# servo.net
KiCad netlist of a schematic drawn in Altium Designer
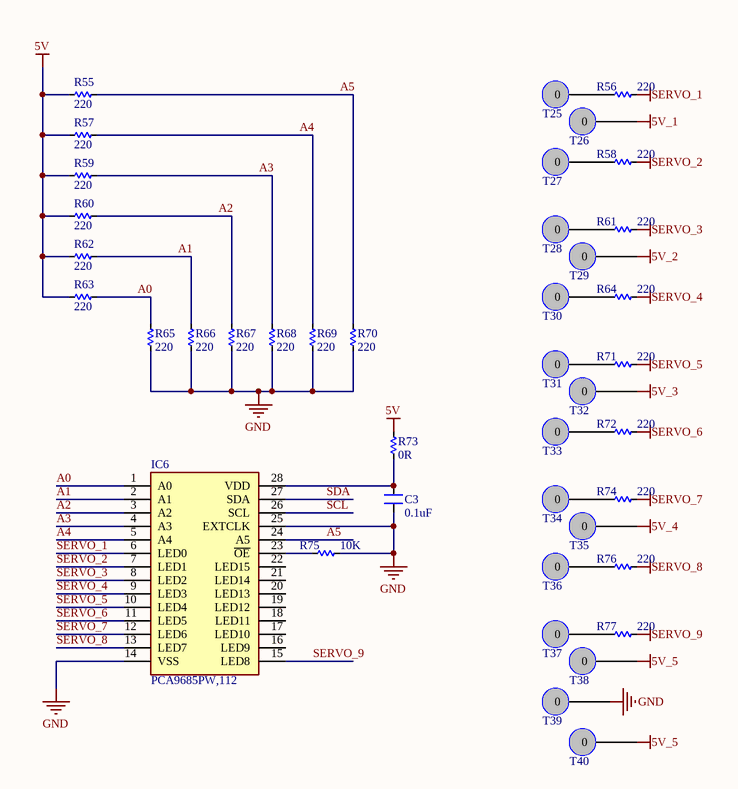
[diagram p0: servo.SchDoc]

(export (version "E")
  (design (tool "Eeschema 10.0.6"))
  (components
    (comp (ref "C3")
      (value "0.1uF")
      (footprint "CN-SMD-0603")
      (description "Tu gom")
      (libsource (lib "LIBTanCN") (part "CN"))
    )
    (comp (ref "IC6")
      (value "PCA9685PW,112")
      (footprint "SamacSys:SOP65P640X110-28N")
      (description "Integrated Circuit")
      (fields (field (name "MOUSER PART NUMBER") "771-PCA9685PW,112"))
      (libsource (lib "*") (part "PCA9685PW,112"))
    )
    (comp (ref "R55")
      (value "220")
      (footprint "RES-SMD-0603")
      (description "Resistor")
      (fields
        (field (name "MANUFACTURER") "Generic Components")
        (field (name "PUBLISHER") "Altium Hobart Technology Centre")
      )
      (libsource (lib "LIBRARY") (part "Res-SMD"))
    )
    (comp (ref "R56")
      (value "220")
      (footprint "RES-SMD-0603")
      (description "Resistor")
      (fields
        (field (name "MANUFACTURER") "Generic Components")
        (field (name "PUBLISHER") "Altium Hobart Technology Centre")
      )
      (libsource (lib "LIBRARY") (part "Res-SMD"))
    )
    (comp (ref "R57")
      (value "220")
      (footprint "RES-SMD-0603")
      (description "Resistor")
      (fields
        (field (name "MANUFACTURER") "Generic Components")
        (field (name "PUBLISHER") "Altium Hobart Technology Centre")
      )
      (libsource (lib "LIBRARY") (part "Res-SMD"))
    )
    (comp (ref "R58")
      (value "220")
      (footprint "RES-SMD-0603")
      (description "Resistor")
      (fields
        (field (name "MANUFACTURER") "Generic Components")
        (field (name "PUBLISHER") "Altium Hobart Technology Centre")
      )
      (libsource (lib "LIBRARY") (part "Res-SMD"))
    )
    (comp (ref "R59")
      (value "220")
      (footprint "RES-SMD-0603")
      (description "Resistor")
      (fields
        (field (name "MANUFACTURER") "Generic Components")
        (field (name "PUBLISHER") "Altium Hobart Technology Centre")
      )
      (libsource (lib "LIBRARY") (part "Res-SMD"))
    )
    (comp (ref "R60")
      (value "220")
      (footprint "RES-SMD-0603")
      (description "Resistor")
      (fields
        (field (name "MANUFACTURER") "Generic Components")
        (field (name "PUBLISHER") "Altium Hobart Technology Centre")
      )
      (libsource (lib "LIBRARY") (part "Res-SMD"))
    )
    (comp (ref "R61")
      (value "220")
      (footprint "RES-SMD-0603")
      (description "Resistor")
      (fields
        (field (name "MANUFACTURER") "Generic Components")
        (field (name "PUBLISHER") "Altium Hobart Technology Centre")
      )
      (libsource (lib "LIBRARY") (part "Res-SMD"))
    )
    (comp (ref "R62")
      (value "220")
      (footprint "RES-SMD-0603")
      (description "Resistor")
      (fields
        (field (name "MANUFACTURER") "Generic Components")
        (field (name "PUBLISHER") "Altium Hobart Technology Centre")
      )
      (libsource (lib "LIBRARY") (part "Res-SMD"))
    )
    (comp (ref "R63")
      (value "220")
      (footprint "RES-SMD-0603")
      (description "Resistor")
      (fields
        (field (name "MANUFACTURER") "Generic Components")
        (field (name "PUBLISHER") "Altium Hobart Technology Centre")
      )
      (libsource (lib "LIBRARY") (part "Res-SMD"))
    )
    (comp (ref "R64")
      (value "220")
      (footprint "RES-SMD-0603")
      (description "Resistor")
      (fields
        (field (name "MANUFACTURER") "Generic Components")
        (field (name "PUBLISHER") "Altium Hobart Technology Centre")
      )
      (libsource (lib "LIBRARY") (part "Res-SMD"))
    )
    (comp (ref "R65")
      (value "220")
      (footprint "RES-SMD-0603")
      (description "Resistor")
      (fields
        (field (name "MANUFACTURER") "Generic Components")
        (field (name "PUBLISHER") "Altium Hobart Technology Centre")
      )
      (libsource (lib "LIBRARY") (part "Res-SMD"))
    )
    (comp (ref "R66")
      (value "220")
      (footprint "RES-SMD-0603")
      (description "Resistor")
      (fields
        (field (name "MANUFACTURER") "Generic Components")
        (field (name "PUBLISHER") "Altium Hobart Technology Centre")
      )
      (libsource (lib "LIBRARY") (part "Res-SMD"))
    )
    (comp (ref "R67")
      (value "220")
      (footprint "RES-SMD-0603")
      (description "Resistor")
      (fields
        (field (name "MANUFACTURER") "Generic Components")
        (field (name "PUBLISHER") "Altium Hobart Technology Centre")
      )
      (libsource (lib "LIBRARY") (part "Res-SMD"))
    )
    (comp (ref "R68")
      (value "220")
      (footprint "RES-SMD-0603")
      (description "Resistor")
      (fields
        (field (name "MANUFACTURER") "Generic Components")
        (field (name "PUBLISHER") "Altium Hobart Technology Centre")
      )
      (libsource (lib "LIBRARY") (part "Res-SMD"))
    )
    (comp (ref "R69")
      (value "220")
      (footprint "RES-SMD-0603")
      (description "Resistor")
      (fields
        (field (name "MANUFACTURER") "Generic Components")
        (field (name "PUBLISHER") "Altium Hobart Technology Centre")
      )
      (libsource (lib "LIBRARY") (part "Res-SMD"))
    )
    (comp (ref "R70")
      (value "220")
      (footprint "RES-SMD-0603")
      (description "Resistor")
      (fields
        (field (name "MANUFACTURER") "Generic Components")
        (field (name "PUBLISHER") "Altium Hobart Technology Centre")
      )
      (libsource (lib "LIBRARY") (part "Res-SMD"))
    )
    (comp (ref "R71")
      (value "220")
      (footprint "RES-SMD-0603")
      (description "Resistor")
      (fields
        (field (name "MANUFACTURER") "Generic Components")
        (field (name "PUBLISHER") "Altium Hobart Technology Centre")
      )
      (libsource (lib "LIBRARY") (part "Res-SMD"))
    )
    (comp (ref "R72")
      (value "220")
      (footprint "RES-SMD-0603")
      (description "Resistor")
      (fields
        (field (name "MANUFACTURER") "Generic Components")
        (field (name "PUBLISHER") "Altium Hobart Technology Centre")
      )
      (libsource (lib "LIBRARY") (part "Res-SMD"))
    )
    (comp (ref "R73")
      (value "0R")
      (footprint "RES-SMD-0603")
      (description "Resistor")
      (fields
        (field (name "MANUFACTURER") "Generic Components")
        (field (name "PUBLISHER") "Altium Hobart Technology Centre")
      )
      (libsource (lib "LIBRARY") (part "Res-SMD"))
    )
    (comp (ref "R74")
      (value "220")
      (footprint "RES-SMD-0603")
      (description "Resistor")
      (fields
        (field (name "MANUFACTURER") "Generic Components")
        (field (name "PUBLISHER") "Altium Hobart Technology Centre")
      )
      (libsource (lib "LIBRARY") (part "Res-SMD"))
    )
    (comp (ref "R75")
      (value "10K")
      (footprint "RES-SMD-0603")
      (description "Resistor")
      (fields
        (field (name "MANUFACTURER") "Generic Components")
        (field (name "PUBLISHER") "Altium Hobart Technology Centre")
      )
      (libsource (lib "LIBRARY") (part "Res-SMD"))
    )
    (comp (ref "R76")
      (value "220")
      (footprint "RES-SMD-0603")
      (description "Resistor")
      (fields
        (field (name "MANUFACTURER") "Generic Components")
        (field (name "PUBLISHER") "Altium Hobart Technology Centre")
      )
      (libsource (lib "LIBRARY") (part "Res-SMD"))
    )
    (comp (ref "R77")
      (value "220")
      (footprint "RES-SMD-0603")
      (description "Resistor")
      (fields
        (field (name "MANUFACTURER") "Generic Components")
        (field (name "PUBLISHER") "Altium Hobart Technology Centre")
      )
      (libsource (lib "LIBRARY") (part "Res-SMD"))
    )
    (comp (ref "T25")
      (value "Pad")
      (footprint "pad_ina:PCBComponent_1")
      (description "pad")
      (libsource (lib "pad_ina") (part "Component_1"))
    )
    (comp (ref "T26")
      (value "Pad")
      (footprint "pad_ina:PCBComponent_1")
      (description "pad")
      (libsource (lib "pad_ina") (part "Component_1"))
    )
    (comp (ref "T27")
      (value "Pad")
      (footprint "pad_ina:PCBComponent_1")
      (description "pad")
      (libsource (lib "pad_ina") (part "Component_1"))
    )
    (comp (ref "T28")
      (value "Pad")
      (footprint "pad_ina:PCBComponent_1")
      (description "pad")
      (libsource (lib "pad_ina") (part "Component_1"))
    )
    (comp (ref "T29")
      (value "Pad")
      (footprint "pad_ina:PCBComponent_1")
      (description "pad")
      (libsource (lib "pad_ina") (part "Component_1"))
    )
    (comp (ref "T30")
      (value "Pad")
      (footprint "pad_ina:PCBComponent_1")
      (description "pad")
      (libsource (lib "pad_ina") (part "Component_1"))
    )
    (comp (ref "T31")
      (value "Pad")
      (footprint "pad_ina:PCBComponent_1")
      (description "pad")
      (libsource (lib "pad_ina") (part "Component_1"))
    )
    (comp (ref "T32")
      (value "Pad")
      (footprint "pad_ina:PCBComponent_1")
      (description "pad")
      (libsource (lib "pad_ina") (part "Component_1"))
    )
    (comp (ref "T33")
      (value "Pad")
      (footprint "pad_ina:PCBComponent_1")
      (description "pad")
      (libsource (lib "pad_ina") (part "Component_1"))
    )
    (comp (ref "T34")
      (value "Pad")
      (footprint "pad_ina:PCBComponent_1")
      (description "pad")
      (libsource (lib "pad_ina") (part "Component_1"))
    )
    (comp (ref "T35")
      (value "Pad")
      (footprint "pad_ina:PCBComponent_1")
      (description "pad")
      (libsource (lib "pad_ina") (part "Component_1"))
    )
    (comp (ref "T36")
      (value "Pad")
      (footprint "pad_ina:PCBComponent_1")
      (description "pad")
      (libsource (lib "pad_ina") (part "Component_1"))
    )
    (comp (ref "T37")
      (value "Pad")
      (footprint "pad_ina:PCBComponent_1")
      (description "pad")
      (libsource (lib "pad_ina") (part "Component_1"))
    )
    (comp (ref "T38")
      (value "Pad")
      (footprint "pad_ina:PCBComponent_1")
      (description "pad")
      (libsource (lib "pad_ina") (part "Component_1"))
    )
    (comp (ref "T39")
      (value "Pad")
      (footprint "pad_ina:PCBComponent_1")
      (description "pad")
      (libsource (lib "pad_ina") (part "Component_1"))
    )
    (comp (ref "T40")
      (value "Pad")
      (footprint "pad_ina:PCBComponent_1")
      (description "pad")
      (libsource (lib "pad_ina") (part "Component_1"))
    )
  )
  (nets
    (net (code "1") (name "/A0") (class "Default")
      (node (ref "IC6") (pin "1") (pinfunction "A0_1") (pintype "passive"))
      (node (ref "R63") (pin "1") (pinfunction "1_1") (pintype "passive"))
      (node (ref "R65") (pin "1") (pinfunction "1_1") (pintype "passive"))
    )
    (net (code "2") (name "/A1") (class "Default")
      (node (ref "IC6") (pin "2") (pinfunction "A1_2") (pintype "passive"))
      (node (ref "R62") (pin "1") (pinfunction "1_1") (pintype "passive"))
      (node (ref "R66") (pin "1") (pinfunction "1_1") (pintype "passive"))
    )
    (net (code "3") (name "/A2") (class "Default")
      (node (ref "IC6") (pin "3") (pinfunction "A2_3") (pintype "passive"))
      (node (ref "R60") (pin "1") (pinfunction "1_1") (pintype "passive"))
      (node (ref "R67") (pin "1") (pinfunction "1_1") (pintype "passive"))
    )
    (net (code "4") (name "/A3") (class "Default")
      (node (ref "IC6") (pin "4") (pinfunction "A3_4") (pintype "passive"))
      (node (ref "R59") (pin "1") (pinfunction "1_1") (pintype "passive"))
      (node (ref "R68") (pin "1") (pinfunction "1_1") (pintype "passive"))
    )
    (net (code "5") (name "/A4") (class "Default")
      (node (ref "IC6") (pin "5") (pinfunction "A4_5") (pintype "passive"))
      (node (ref "R57") (pin "1") (pinfunction "1_1") (pintype "passive"))
      (node (ref "R69") (pin "1") (pinfunction "1_1") (pintype "passive"))
    )
    (net (code "6") (name "/A5") (class "Default")
      (node (ref "IC6") (pin "24") (pinfunction "A5_24") (pintype "passive"))
      (node (ref "R55") (pin "1") (pinfunction "1_1") (pintype "passive"))
      (node (ref "R70") (pin "1") (pinfunction "1_1") (pintype "passive"))
    )
    (net (code "7") (name "/SCL") (class "Default")
      (node (ref "IC6") (pin "26") (pinfunction "SCL_26") (pintype "passive"))
    )
    (net (code "8") (name "/SDA") (class "Default")
      (node (ref "IC6") (pin "27") (pinfunction "SDA_27") (pintype "passive"))
    )
    (net (code "9") (name "5V") (class "Default")
      (node (ref "R55") (pin "2") (pinfunction "2_2") (pintype "passive"))
      (node (ref "R57") (pin "2") (pinfunction "2_2") (pintype "passive"))
      (node (ref "R59") (pin "2") (pinfunction "2_2") (pintype "passive"))
      (node (ref "R60") (pin "2") (pinfunction "2_2") (pintype "passive"))
      (node (ref "R62") (pin "2") (pinfunction "2_2") (pintype "passive"))
      (node (ref "R63") (pin "2") (pinfunction "2_2") (pintype "passive"))
      (node (ref "R73") (pin "1") (pinfunction "1_1") (pintype "passive"))
    )
    (net (code "10") (name "5V_1") (class "Default")
      (node (ref "T26") (pin "0") (pinfunction "0_0") (pintype "passive"))
    )
    (net (code "11") (name "5V_2") (class "Default")
      (node (ref "T29") (pin "0") (pinfunction "0_0") (pintype "passive"))
    )
    (net (code "12") (name "5V_3") (class "Default")
      (node (ref "T32") (pin "0") (pinfunction "0_0") (pintype "passive"))
    )
    (net (code "13") (name "5V_4") (class "Default")
      (node (ref "T35") (pin "0") (pinfunction "0_0") (pintype "passive"))
    )
    (net (code "14") (name "5V_5") (class "Default")
      (node (ref "T38") (pin "0") (pinfunction "0_0") (pintype "passive"))
      (node (ref "T40") (pin "0") (pinfunction "0_0") (pintype "passive"))
    )
    (net (code "15") (name "GND") (class "Default")
      (node (ref "C3") (pin "1") (pinfunction "1_1") (pintype "passive"))
      (node (ref "IC6") (pin "14") (pinfunction "VSS_14") (pintype "passive"))
      (node (ref "IC6") (pin "25") (pinfunction "EXTCLK_25") (pintype "passive"))
      (node (ref "R65") (pin "2") (pinfunction "2_2") (pintype "passive"))
      (node (ref "R66") (pin "2") (pinfunction "2_2") (pintype "passive"))
      (node (ref "R67") (pin "2") (pinfunction "2_2") (pintype "passive"))
      (node (ref "R68") (pin "2") (pinfunction "2_2") (pintype "passive"))
      (node (ref "R69") (pin "2") (pinfunction "2_2") (pintype "passive"))
      (node (ref "R70") (pin "2") (pinfunction "2_2") (pintype "passive"))
      (node (ref "R75") (pin "2") (pinfunction "2_2") (pintype "passive"))
      (node (ref "T39") (pin "0") (pinfunction "0_0") (pintype "passive"))
    )
    (net (code "16") (name "Net-(IC6-VDD)") (class "Default")
      (node (ref "C3") (pin "2") (pinfunction "2_2") (pintype "passive"))
      (node (ref "IC6") (pin "28") (pinfunction "VDD_28") (pintype "passive"))
      (node (ref "R73") (pin "2") (pinfunction "2_2") (pintype "passive"))
    )
    (net (code "17") (name "Net-(IC6-~{OE})") (class "Default")
      (node (ref "IC6") (pin "23") (pinfunction "~{OE}_23") (pintype "passive"))
      (node (ref "R75") (pin "1") (pinfunction "1_1") (pintype "passive"))
    )
    (net (code "18") (name "Net-(R56-Pad2)") (class "Default")
      (node (ref "R56") (pin "2") (pinfunction "2_2") (pintype "passive"))
      (node (ref "T25") (pin "0") (pinfunction "0_0") (pintype "passive"))
    )
    (net (code "19") (name "Net-(R58-Pad2)") (class "Default")
      (node (ref "R58") (pin "2") (pinfunction "2_2") (pintype "passive"))
      (node (ref "T27") (pin "0") (pinfunction "0_0") (pintype "passive"))
    )
    (net (code "20") (name "Net-(R61-Pad2)") (class "Default")
      (node (ref "R61") (pin "2") (pinfunction "2_2") (pintype "passive"))
      (node (ref "T28") (pin "0") (pinfunction "0_0") (pintype "passive"))
    )
    (net (code "21") (name "Net-(R64-Pad2)") (class "Default")
      (node (ref "R64") (pin "2") (pinfunction "2_2") (pintype "passive"))
      (node (ref "T30") (pin "0") (pinfunction "0_0") (pintype "passive"))
    )
    (net (code "22") (name "Net-(R71-Pad2)") (class "Default")
      (node (ref "R71") (pin "2") (pinfunction "2_2") (pintype "passive"))
      (node (ref "T31") (pin "0") (pinfunction "0_0") (pintype "passive"))
    )
    (net (code "23") (name "Net-(R72-Pad2)") (class "Default")
      (node (ref "R72") (pin "2") (pinfunction "2_2") (pintype "passive"))
      (node (ref "T33") (pin "0") (pinfunction "0_0") (pintype "passive"))
    )
    (net (code "24") (name "Net-(R74-Pad2)") (class "Default")
      (node (ref "R74") (pin "2") (pinfunction "2_2") (pintype "passive"))
      (node (ref "T34") (pin "0") (pinfunction "0_0") (pintype "passive"))
    )
    (net (code "25") (name "Net-(R76-Pad2)") (class "Default")
      (node (ref "R76") (pin "2") (pinfunction "2_2") (pintype "passive"))
      (node (ref "T36") (pin "0") (pinfunction "0_0") (pintype "passive"))
    )
    (net (code "26") (name "Net-(R77-Pad2)") (class "Default")
      (node (ref "R77") (pin "2") (pinfunction "2_2") (pintype "passive"))
      (node (ref "T37") (pin "0") (pinfunction "0_0") (pintype "passive"))
    )
    (net (code "27") (name "SERVO_1") (class "Default")
      (node (ref "IC6") (pin "6") (pinfunction "LED0_6") (pintype "passive"))
      (node (ref "R56") (pin "1") (pinfunction "1_1") (pintype "passive"))
    )
    (net (code "28") (name "SERVO_2") (class "Default")
      (node (ref "IC6") (pin "7") (pinfunction "LED1_7") (pintype "passive"))
      (node (ref "R58") (pin "1") (pinfunction "1_1") (pintype "passive"))
    )
    (net (code "29") (name "SERVO_3") (class "Default")
      (node (ref "IC6") (pin "8") (pinfunction "LED2_8") (pintype "passive"))
      (node (ref "R61") (pin "1") (pinfunction "1_1") (pintype "passive"))
    )
    (net (code "30") (name "SERVO_4") (class "Default")
      (node (ref "IC6") (pin "9") (pinfunction "LED3_9") (pintype "passive"))
      (node (ref "R64") (pin "1") (pinfunction "1_1") (pintype "passive"))
    )
    (net (code "31") (name "SERVO_5") (class "Default")
      (node (ref "IC6") (pin "10") (pinfunction "LED4_10") (pintype "passive"))
      (node (ref "R71") (pin "1") (pinfunction "1_1") (pintype "passive"))
    )
    (net (code "32") (name "SERVO_6") (class "Default")
      (node (ref "IC6") (pin "11") (pinfunction "LED5_11") (pintype "passive"))
      (node (ref "R72") (pin "1") (pinfunction "1_1") (pintype "passive"))
    )
    (net (code "33") (name "SERVO_7") (class "Default")
      (node (ref "IC6") (pin "12") (pinfunction "LED6_12") (pintype "passive"))
      (node (ref "R74") (pin "1") (pinfunction "1_1") (pintype "passive"))
    )
    (net (code "34") (name "SERVO_8") (class "Default")
      (node (ref "IC6") (pin "13") (pinfunction "LED7_13") (pintype "passive"))
      (node (ref "R76") (pin "1") (pinfunction "1_1") (pintype "passive"))
    )
    (net (code "35") (name "SERVO_9") (class "Default")
      (node (ref "IC6") (pin "15") (pinfunction "LED8_15") (pintype "passive"))
      (node (ref "R77") (pin "1") (pinfunction "1_1") (pintype "passive"))
    )
    (net (code "36") (name "unconnected-(IC6-LED9-Pad16)") (class "Default")
      (node (ref "IC6") (pin "16") (pinfunction "LED9_16") (pintype "passive"))
    )
    (net (code "37") (name "unconnected-(IC6-LED10-Pad17)") (class "Default")
      (node (ref "IC6") (pin "17") (pinfunction "LED10_17") (pintype "passive"))
    )
    (net (code "38") (name "unconnected-(IC6-LED11-Pad18)") (class "Default")
      (node (ref "IC6") (pin "18") (pinfunction "LED11_18") (pintype "passive"))
    )
    (net (code "39") (name "unconnected-(IC6-LED12-Pad19)") (class "Default")
      (node (ref "IC6") (pin "19") (pinfunction "LED12_19") (pintype "passive"))
    )
    (net (code "40") (name "unconnected-(IC6-LED13-Pad20)") (class "Default")
      (node (ref "IC6") (pin "20") (pinfunction "LED13_20") (pintype "passive"))
    )
    (net (code "41") (name "unconnected-(IC6-LED14-Pad21)") (class "Default")
      (node (ref "IC6") (pin "21") (pinfunction "LED14_21") (pintype "passive"))
    )
    (net (code "42") (name "unconnected-(IC6-LED15-Pad22)") (class "Default")
      (node (ref "IC6") (pin "22") (pinfunction "LED15_22") (pintype "passive"))
    )
  )
)
